# 15V7A.net
KiCad netlist of a schematic drawn in Altium Designer
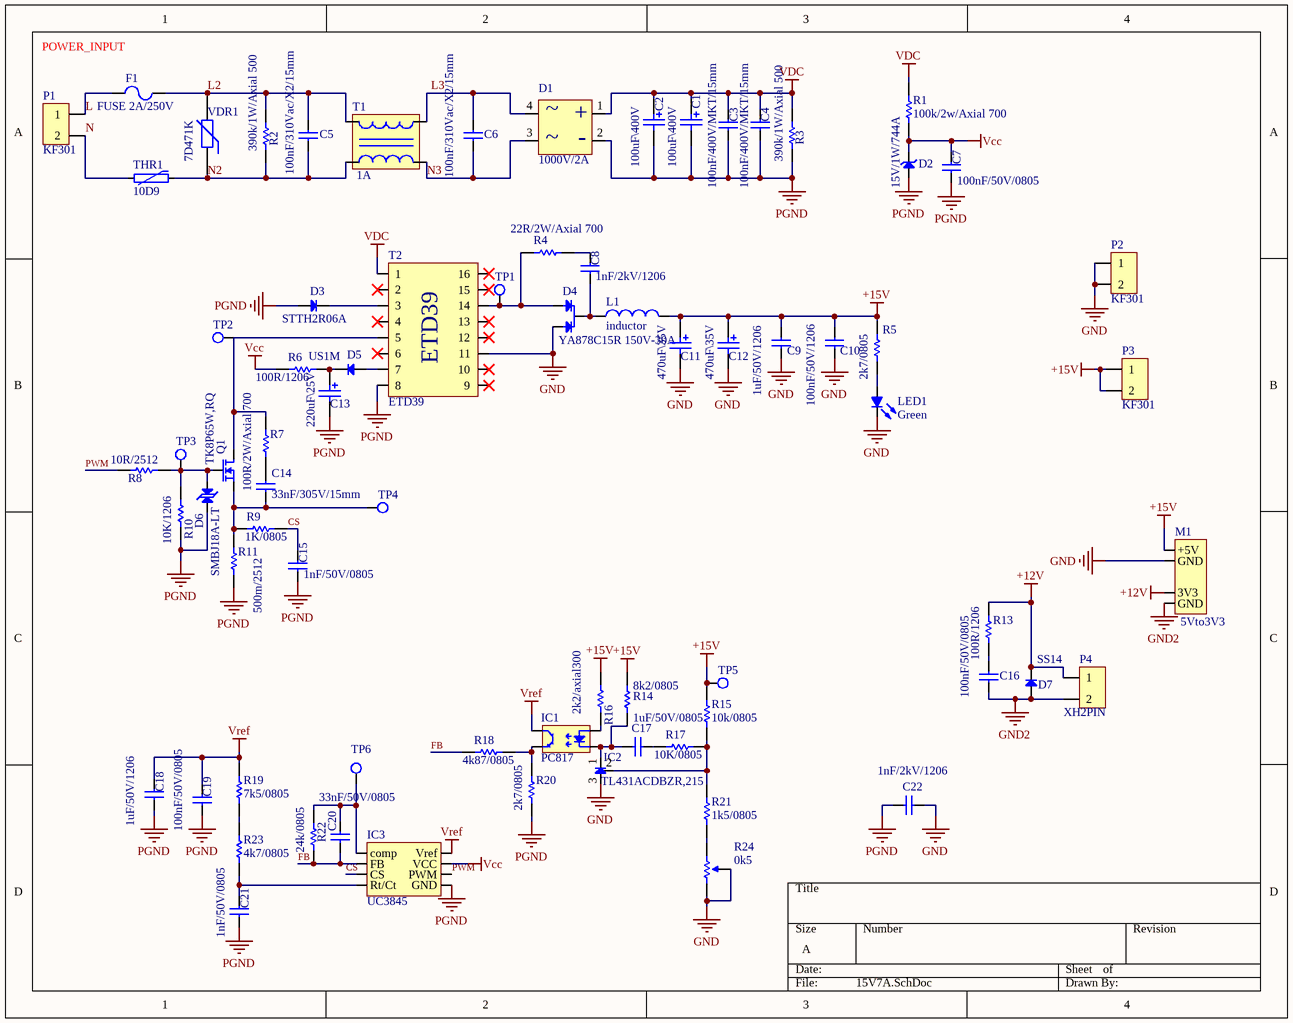
[diagram p0: 15V7A.SchDoc]

(export (version "E")
  (design (tool "Eeschema 10.0.6"))
  (components
    (comp (ref "C1")
      (value "100u~{F}400V")
      (footprint "18.5x31 p = 7.5")
      (description "Polarized Capacitor (Radial)")
      (fields (field (name "PUBLISHER") "Altium Limited"))
      (libsource (lib "Schlib") (part "Cap Pol1"))
    )
    (comp (ref "C2")
      (value "100u~{F}400V")
      (footprint "18.5x31 p = 7.5")
      (description "Polarized Capacitor (Radial)")
      (fields (field (name "PUBLISHER") "Altium Limited"))
      (libsource (lib "Schlib") (part "Cap Pol1"))
    )
    (comp (ref "C3")
      (value "100nF/400V/MKT/15mm")
      (footprint "18.4x7.5 p =15")
      (description "Capacitor")
      (libsource (lib "Schlib") (part "Capacitor"))
    )
    (comp (ref "C4")
      (value "100nF/400V/MKT/15mm")
      (footprint "18.4x7.5 p =15")
      (description "Capacitor")
      (libsource (lib "Schlib") (part "Capacitor"))
    )
    (comp (ref "C5")
      (value "100nF/310Vac/X2/15mm")
      (footprint "0.1uF/275VAC/X@/15mm")
      (description "Capacitor")
      (libsource (lib "Schlib") (part "Capacitor"))
    )
    (comp (ref "C6")
      (value "100nF/310Vac/X2/15mm")
      (footprint "0.1uF/275VAC/X@/15mm")
      (description "Capacitor")
      (libsource (lib "Schlib") (part "Capacitor"))
    )
    (comp (ref "C7")
      (value "100nF/50V/0805")
      (footprint "CAP 0805")
      (description "Capacitor")
      (libsource (lib "Schlib") (part "Capacitor"))
    )
    (comp (ref "C8")
      (value "1nF/2kV/1206")
      (footprint "CAP 1206")
      (description "Capacitor")
      (libsource (lib "Schlib") (part "Capacitor"))
    )
    (comp (ref "C9")
      (value "1uF/50V/1206")
      (footprint "CAP 1206")
      (description "Capacitor")
      (libsource (lib "Schlib") (part "Capacitor"))
    )
    (comp (ref "C10")
      (value "100nF/50V/1206")
      (footprint "CAP 1206")
      (description "Capacitor")
      (libsource (lib "Schlib") (part "Capacitor"))
    )
    (comp (ref "C11")
      (value "470u~{F}35V")
      (footprint "10x12 p = 5")
      (description "Polarized Capacitor (Radial)")
      (fields (field (name "PUBLISHER") "Altium Limited"))
      (libsource (lib "Schlib") (part "Cap Pol1"))
    )
    (comp (ref "C12")
      (value "470u~{F}35V")
      (footprint "10x12 p = 5")
      (description "Polarized Capacitor (Radial)")
      (fields (field (name "PUBLISHER") "Altium Limited"))
      (libsource (lib "Schlib") (part "Cap Pol1"))
    )
    (comp (ref "C13")
      (value "220u~{F}25V")
      (footprint "cap 5*11,p=2")
      (description "Polarized Capacitor (Radial)")
      (fields (field (name "PUBLISHER") "Altium Limited"))
      (libsource (lib "Schlib") (part "Cap Pol1"))
    )
    (comp (ref "C14")
      (value "33nF/305V/15mm")
      (footprint "0.1uF/275VAC/X@/15mm")
      (description "Capacitor")
      (libsource (lib "Schlib") (part "Capacitor"))
    )
    (comp (ref "C15")
      (value "1nF/50V/0805")
      (footprint "CAP 0805")
      (description "Capacitor")
      (libsource (lib "Schlib") (part "Capacitor"))
    )
    (comp (ref "C16")
      (value "100nF/50V/0805")
      (footprint "CAP 0805")
      (description "Capacitor")
      (libsource (lib "Schlib") (part "Capacitor"))
    )
    (comp (ref "C17")
      (value "1uF/50V/0805")
      (footprint "CAP 0805")
      (description "Capacitor")
      (libsource (lib "Schlib") (part "Capacitor"))
    )
    (comp (ref "C18")
      (value "1uF/50V/1206")
      (footprint "CAP 1206")
      (description "Capacitor")
      (libsource (lib "Schlib") (part "Capacitor"))
    )
    (comp (ref "C19")
      (value "100nF/50V/0805")
      (footprint "CAP 0805")
      (description "Capacitor")
      (libsource (lib "Schlib") (part "Capacitor"))
    )
    (comp (ref "C20")
      (value "33nF/50V/0805")
      (footprint "CAP 0805")
      (description "Capacitor")
      (libsource (lib "Schlib") (part "Capacitor"))
    )
    (comp (ref "C21")
      (value "1nF/50V/0805")
      (footprint "CAP 0805")
      (description "Capacitor")
      (libsource (lib "Schlib") (part "Capacitor"))
    )
    (comp (ref "C22")
      (value "1nF/2kV/1206")
      (footprint "CAP 1206")
      (description "Capacitor")
      (libsource (lib "Schlib") (part "Capacitor"))
    )
    (comp (ref "D1") (value "1000V/2A") (footprint "ABS210") (libsource (lib "Schlib") (part "br-diode")))
    (comp (ref "D2") (value "15V/1W/744A") (footprint "SMA") (libsource (lib "Schlib") (part "ZENER")))
    (comp (ref "D3") (value "STTH2R06A") (footprint "SMA") (libsource (lib "Schlib") (part "Diode")))
    (comp (ref "D4")
      (value "YA878C15R 150V-30A")
      (footprint "TO-220")
      (libsource (lib "Schlib") (part "Diode 2*1 CA"))
    )
    (comp (ref "D5") (value "US1M") (footprint "SMA") (libsource (lib "Schlib") (part "Diode")))
    (comp (ref "D6")
      (value "SMBJ18A-LT")
      (footprint "SMB(DO-214AA)")
      (description "18v-20A")
      (libsource (lib "Schlib") (part "TVS-BIPOLAR"))
    )
    (comp (ref "D7") (value "SS14") (footprint "SMA") (libsource (lib "Schlib") (part "Diode")))
    (comp (ref "F1")
      (value "FUSE 2A/250V")
      (footprint "smd Fuse Block 155 OMNI-BLOK")
      (description "Fuse")
      (libsource (lib "Fx7sam") (part "Fuse"))
    )
    (comp (ref "IC1") (value "PC817") (footprint "pc817") (libsource (lib "Schlib") (part "PC817")))
    (comp (ref "IC2")
      (value "TL431ACDBZR,215")
      (footprint "SOT-23")
      (libsource (lib "Schlib") (part "TL431DBZ"))
    )
    (comp (ref "IC3") (value "UC3845") (footprint "SO8") (libsource (lib "Schlib") (part "UC3845")))
    (comp (ref "L1")
      (value "inductor")
      (footprint "50uh/kt130-26")
      (libsource (lib "Schlib") (part "inductor"))
    )
    (comp (ref "LED1")
      (value "LED 3mm/Green")
      (footprint "LED 3mm")
      (description "Typical LED")
      (fields (field (name "COLOR") "Green"))
      (libsource (lib "TL494 12V-20A-KARA") (part "LED"))
    )
    (comp (ref "M1") (value "5Vto3V3") (footprint "5Vto3V3") (libsource (lib "Schlib") (part "5Vto3V3")))
    (comp (ref "P1")
      (value "KF301")
      (footprint "KF301-5.0-2P")
      (description "RELAY")
      (fields (field (name "PUBLISHER") "Altium Limited"))
      (libsource (lib "Schlib") (part "Header 2H"))
    )
    (comp (ref "P2")
      (value "KF301")
      (footprint "KF301-5.0-2P")
      (description "RELAY")
      (fields (field (name "PUBLISHER") "Altium Limited"))
      (libsource (lib "") (part "Header 2H_1"))
    )
    (comp (ref "P3")
      (value "KF301")
      (footprint "KF301-5.0-2P")
      (description "RELAY")
      (fields (field (name "PUBLISHER") "Altium Limited"))
      (libsource (lib "") (part "Header 2H_1"))
    )
    (comp (ref "P4")
      (value "XH2PIN")
      (footprint "XH-2Pin")
      (description "RELAY")
      (fields (field (name "PUBLISHER") "Altium Limited"))
      (libsource (lib "") (part "Header 2H_1"))
    )
    (comp (ref "Q1")
      (value "TK8P65W,RQ")
      (footprint "DPAK-3")
      (libsource (lib "Schlib") (part "Mosfet N-channel"))
    )
    (comp (ref "R1")
      (value "100k/2w/Axial 700")
      (footprint "Axial 0.7")
      (libsource (lib "Schlib") (part "Res"))
    )
    (comp (ref "R2")
      (value "390k/1W/Axial 500")
      (footprint "RES 2512")
      (libsource (lib "Schlib") (part "Res"))
    )
    (comp (ref "R3")
      (value "390k/1W/Axial 500")
      (footprint "RES 2512")
      (libsource (lib "Schlib") (part "Res"))
    )
    (comp (ref "R4")
      (value "22R/2W/Axial 700")
      (footprint "Axial 0.7")
      (description "Resistor")
      (fields (field (name "PUBLISHER") "Altium Limited"))
      (libsource (lib "Miscellaneous Devices") (part "Res1"))
    )
    (comp (ref "R5")
      (value "2k7/0805")
      (footprint "RES 0805")
      (description "Resistor")
      (fields (field (name "PUBLISHER") "Altium Limited"))
      (libsource (lib "Miscellaneous Devices") (part "Res1"))
    )
    (comp (ref "R6")
      (value "100R/1206")
      (footprint "RES 1206")
      (description "Resistor")
      (fields (field (name "PUBLISHER") "Altium Limited"))
      (libsource (lib "Miscellaneous Devices") (part "Res1"))
    )
    (comp (ref "R7")
      (value "100R/2W/Axial 700")
      (footprint "Axial 0.7")
      (description "Resistor")
      (fields (field (name "PUBLISHER") "Altium Limited"))
      (libsource (lib "Miscellaneous Devices") (part "Res1"))
    )
    (comp (ref "R8")
      (value "10R/2512")
      (footprint "RES 2512")
      (description "Resistor")
      (fields (field (name "PUBLISHER") "Altium Limited"))
      (libsource (lib "Miscellaneous Devices") (part "Res1"))
    )
    (comp (ref "R9")
      (value "1K/0805")
      (footprint "RES 0805")
      (description "Resistor")
      (fields (field (name "PUBLISHER") "Altium Limited"))
      (libsource (lib "Miscellaneous Devices") (part "Res1"))
    )
    (comp (ref "R10")
      (value "10K/1206")
      (footprint "RES 1206")
      (description "Resistor")
      (fields (field (name "PUBLISHER") "Altium Limited"))
      (libsource (lib "Miscellaneous Devices") (part "Res1"))
    )
    (comp (ref "R11")
      (value "500m/2512")
      (footprint "RES 1206")
      (description "Resistor")
      (fields (field (name "PUBLISHER") "Altium Limited"))
      (libsource (lib "Miscellaneous Devices") (part "Res1"))
    )
    (comp (ref "R13") (value "100R/1206") (footprint "RES 1206") (libsource (lib "22") (part "Res 0.5 W")))
    (comp (ref "R14")
      (value "8k2/0805")
      (footprint "RES 0805")
      (description "Resistor")
      (fields (field (name "PUBLISHER") "Altium Limited"))
      (libsource (lib "Miscellaneous Devices") (part "Res1"))
    )
    (comp (ref "R15")
      (value "10k/0805")
      (footprint "RES 0805")
      (description "Resistor")
      (fields (field (name "PUBLISHER") "Altium Limited"))
      (libsource (lib "Miscellaneous Devices") (part "Res1"))
    )
    (comp (ref "R16")
      (value "2k2/axial300")
      (footprint "Axial 0.3")
      (description "Resistor")
      (fields (field (name "PUBLISHER") "Altium Limited"))
      (libsource (lib "Miscellaneous Devices") (part "Res1"))
    )
    (comp (ref "R17")
      (value "10K/0805")
      (footprint "RES 0805")
      (description "Resistor")
      (fields (field (name "PUBLISHER") "Altium Limited"))
      (libsource (lib "Miscellaneous Devices") (part "Res1"))
    )
    (comp (ref "R18")
      (value "4k87/0805")
      (footprint "RES 0805")
      (description "Resistor")
      (fields (field (name "PUBLISHER") "Altium Limited"))
      (libsource (lib "Miscellaneous Devices") (part "Res1"))
    )
    (comp (ref "R19")
      (value "7k5/0805")
      (footprint "RES 0805")
      (description "Resistor")
      (fields (field (name "PUBLISHER") "Altium Limited"))
      (libsource (lib "Miscellaneous Devices") (part "Res1"))
    )
    (comp (ref "R20")
      (value "2k7/0805")
      (footprint "RES 0805")
      (description "Resistor")
      (fields (field (name "PUBLISHER") "Altium Limited"))
      (libsource (lib "Miscellaneous Devices") (part "Res1"))
    )
    (comp (ref "R21")
      (value "1k5/0805")
      (footprint "RES 0805")
      (description "Resistor")
      (fields (field (name "PUBLISHER") "Altium Limited"))
      (libsource (lib "Miscellaneous Devices") (part "Res1"))
    )
    (comp (ref "R22")
      (value "24k/0805")
      (footprint "RES 0805")
      (description "Resistor")
      (fields (field (name "PUBLISHER") "Altium Limited"))
      (libsource (lib "Miscellaneous Devices") (part "Res1"))
    )
    (comp (ref "R23")
      (value "4k7/0805")
      (footprint "RES 0805")
      (description "Resistor")
      (fields (field (name "PUBLISHER") "Altium Limited"))
      (libsource (lib "Miscellaneous Devices") (part "Res1"))
    )
    (comp (ref "R24")
      (value "0k5")
      (footprint "trimmer resistor thd")
      (libsource (lib "Schlib") (part "POT"))
    )
    (comp (ref "T1")
      (value "1A")
      (footprint "UF 10")
      (description "Line Filter")
      (libsource (lib "Fx7sam") (part "Line Filter_01"))
    )
    (comp (ref "T2") (value "ETD39") (footprint "ETD39 - forward") (libsource (lib "Schlib") (part "ETD39")))
    (comp (ref "THR1")
      (value "10D9")
      (footprint "10D9")
      (description "NTC")
      (libsource (lib "CHARGER 99-02") (part "NTC"))
    )
    (comp (ref "TP1") (value "~") (footprint "TP") (libsource (lib "Schlib") (part "test-point")))
    (comp (ref "TP2") (value "~") (footprint "TP") (libsource (lib "Schlib") (part "test-point")))
    (comp (ref "TP3") (value "~") (footprint "TP") (libsource (lib "Schlib") (part "test-point")))
    (comp (ref "TP4") (value "~") (footprint "TP") (libsource (lib "Schlib") (part "test-point")))
    (comp (ref "TP5") (value "~") (footprint "TP") (libsource (lib "Schlib") (part "test-point")))
    (comp (ref "TP6") (value "~") (footprint "TP") (libsource (lib "Schlib") (part "test-point")))
    (comp (ref "VDR1")
      (value "7D471K")
      (footprint "7D471K")
      (description "VARISTORS")
      (fields
        (field (name "MANUFACTURER") "china-canada-philipina")
        (field (name "DESIGNER") "Abbas Basereh")
        (field (name "PUBLISHER") "ABBAS BASEREH")
      )
      (libsource (lib "reza babatabar (8)") (part "VARISTOR (VDR)"))
    )
  )
  (nets
    (net (code "1") (name "+12V") (class "Default")
      (node (ref "D7") (pin "2") (pinfunction "2_2") (pintype "passive"))
      (node (ref "M1") (pin "3") (pinfunction "3V3_3") (pintype "passive"))
      (node (ref "P4") (pin "1") (pinfunction "1_1") (pintype "passive"))
      (node (ref "R13") (pin "1") (pinfunction "1_1") (pintype "passive"))
    )
    (net (code "2") (name "+15V") (class "Default")
      (node (ref "C10") (pin "2") (pinfunction "-_2") (pintype "passive"))
      (node (ref "C11") (pin "1") (pinfunction "1_1") (pintype "passive"))
      (node (ref "C12") (pin "1") (pinfunction "1_1") (pintype "passive"))
      (node (ref "C9") (pin "2") (pinfunction "-_2") (pintype "passive"))
      (node (ref "L1") (pin "2") (pinfunction "2_2") (pintype "passive"))
      (node (ref "M1") (pin "1") (pinfunction "+5V_1") (pintype "passive"))
      (node (ref "P3") (pin "1") (pinfunction "1_1") (pintype "passive"))
      (node (ref "P3") (pin "2") (pinfunction "2_2") (pintype "passive"))
      (node (ref "R14") (pin "1") (pinfunction "1_1") (pintype "passive"))
      (node (ref "R15") (pin "1") (pinfunction "1_1") (pintype "passive"))
      (node (ref "R16") (pin "1") (pinfunction "1_1") (pintype "passive"))
      (node (ref "R5") (pin "1") (pinfunction "1_1") (pintype "passive"))
      (node (ref "TP5") (pin "1") (pintype "passive"))
    )
    (net (code "3") (name "/CS") (class "Default")
      (node (ref "C15") (pin "2") (pinfunction "-_2") (pintype "passive"))
      (node (ref "IC3") (pin "3") (pinfunction "CS_3") (pintype "passive"))
      (node (ref "R9") (pin "1") (pinfunction "1_1") (pintype "passive"))
    )
    (net (code "4") (name "/FB") (class "Default")
      (node (ref "C20") (pin "1") (pinfunction "+_1") (pintype "passive"))
      (node (ref "IC3") (pin "2") (pinfunction "FB_2") (pintype "passive"))
      (node (ref "R18") (pin "1") (pinfunction "1_1") (pintype "passive"))
      (node (ref "R22") (pin "2") (pinfunction "2_2") (pintype "passive"))
    )
    (net (code "5") (name "/L") (class "Default")
      (node (ref "F1") (pin "2") (pinfunction "2_2") (pintype "passive"))
      (node (ref "P1") (pin "1") (pinfunction "1_1") (pintype "passive"))
    )
    (net (code "6") (name "/L2") (class "Default")
      (node (ref "C5") (pin "1") (pinfunction "+_1") (pintype "passive"))
      (node (ref "F1") (pin "1") (pinfunction "1_1") (pintype "passive"))
      (node (ref "R2") (pin "2") (pinfunction "2_2") (pintype "passive"))
      (node (ref "T1") (pin "1") (pinfunction "1_1") (pintype "passive"))
      (node (ref "VDR1") (pin "2") (pinfunction "2_2") (pintype "passive"))
    )
    (net (code "7") (name "/L3") (class "Default")
      (node (ref "C6") (pin "2") (pinfunction "-_2") (pintype "passive"))
      (node (ref "D1") (pin "4") (pinfunction "4_4") (pintype "passive"))
      (node (ref "T1") (pin "4") (pinfunction "4_4") (pintype "passive"))
    )
    (net (code "8") (name "/N") (class "Default")
      (node (ref "P1") (pin "2") (pinfunction "2_2") (pintype "passive"))
      (node (ref "THR1") (pin "2") (pinfunction "2_2") (pintype "passive"))
    )
    (net (code "9") (name "/N2") (class "Default")
      (node (ref "C5") (pin "2") (pinfunction "-_2") (pintype "passive"))
      (node (ref "R2") (pin "1") (pinfunction "1_1") (pintype "passive"))
      (node (ref "T1") (pin "2") (pinfunction "2_2") (pintype "passive"))
      (node (ref "THR1") (pin "1") (pinfunction "1_1") (pintype "passive"))
      (node (ref "VDR1") (pin "1") (pinfunction "1_1") (pintype "passive"))
    )
    (net (code "10") (name "/N3") (class "Default")
      (node (ref "C6") (pin "1") (pinfunction "+_1") (pintype "passive"))
      (node (ref "D1") (pin "3") (pinfunction "3_3") (pintype "passive"))
      (node (ref "T1") (pin "3") (pinfunction "3_3") (pintype "passive"))
    )
    (net (code "11") (name "/PWM") (class "Default")
      (node (ref "IC3") (pin "6") (pinfunction "PWM_6") (pintype "passive"))
      (node (ref "R8") (pin "1") (pinfunction "1_1") (pintype "passive"))
    )
    (net (code "12") (name "GND") (class "Default")
      (node (ref "C10") (pin "1") (pinfunction "+_1") (pintype "passive"))
      (node (ref "C11") (pin "2") (pinfunction "2_2") (pintype "passive"))
      (node (ref "C12") (pin "2") (pinfunction "2_2") (pintype "passive"))
      (node (ref "C22") (pin "1") (pinfunction "+_1") (pintype "passive"))
      (node (ref "C9") (pin "1") (pinfunction "+_1") (pintype "passive"))
      (node (ref "D4") (pin "1") (pinfunction "1_1") (pintype "passive"))
      (node (ref "IC2") (pin "3") (pinfunction "Anode_3") (pintype "passive"))
      (node (ref "LED1") (pin "2") (pinfunction "K_2") (pintype "passive"))
      (node (ref "M1") (pin "2") (pinfunction "GND_2") (pintype "passive"))
      (node (ref "P2") (pin "1") (pinfunction "1_1") (pintype "passive"))
      (node (ref "P2") (pin "2") (pinfunction "2_2") (pintype "passive"))
      (node (ref "R24") (pin "2") (pinfunction "2_2") (pintype "passive"))
      (node (ref "R24") (pin "3") (pinfunction "3_3") (pintype "passive"))
      (node (ref "T2") (pin "11") (pinfunction "11_11") (pintype "passive"))
    )
    (net (code "13") (name "GND2") (class "Default")
      (node (ref "C16") (pin "1") (pinfunction "+_1") (pintype "passive"))
      (node (ref "D7") (pin "1") (pinfunction "1_1") (pintype "passive"))
      (node (ref "M1") (pin "4") (pinfunction "GND_4") (pintype "passive"))
      (node (ref "P4") (pin "2") (pinfunction "2_2") (pintype "passive"))
    )
    (net (code "14") (name "Net-(C8-+)") (class "Default")
      (node (ref "C8") (pin "1") (pinfunction "+_1") (pintype "passive"))
      (node (ref "D4") (pin "2") (pinfunction "2_2") (pintype "passive"))
      (node (ref "L1") (pin "1") (pinfunction "1_1") (pintype "passive"))
    )
    (net (code "15") (name "Net-(C8--)") (class "Default")
      (node (ref "C8") (pin "2") (pinfunction "-_2") (pintype "passive"))
      (node (ref "R4") (pin "1") (pinfunction "1_1") (pintype "passive"))
    )
    (net (code "16") (name "Net-(C13-Pad1)") (class "Default")
      (node (ref "C13") (pin "1") (pinfunction "1_1") (pintype "passive"))
      (node (ref "D5") (pin "2") (pinfunction "2_2") (pintype "passive"))
      (node (ref "R6") (pin "2") (pinfunction "2_2") (pintype "passive"))
    )
    (net (code "17") (name "Net-(C14-+)") (class "Default")
      (node (ref "C14") (pin "1") (pinfunction "+_1") (pintype "passive"))
      (node (ref "Q1") (pin "3") (pinfunction "S_3") (pintype "passive"))
      (node (ref "R11") (pin "1") (pinfunction "1_1") (pintype "passive"))
      (node (ref "R9") (pin "2") (pinfunction "2_2") (pintype "passive"))
      (node (ref "TP4") (pin "1") (pintype "passive"))
    )
    (net (code "18") (name "Net-(C14--)") (class "Default")
      (node (ref "C14") (pin "2") (pinfunction "-_2") (pintype "passive"))
      (node (ref "R7") (pin "2") (pinfunction "2_2") (pintype "passive"))
    )
    (net (code "19") (name "Net-(C16--)") (class "Default")
      (node (ref "C16") (pin "2") (pinfunction "-_2") (pintype "passive"))
      (node (ref "R13") (pin "2") (pinfunction "2_2") (pintype "passive"))
    )
    (net (code "20") (name "Net-(C17-+)") (class "Default")
      (node (ref "C17") (pin "1") (pinfunction "+_1") (pintype "passive"))
      (node (ref "R17") (pin "1") (pinfunction "1_1") (pintype "passive"))
    )
    (net (code "21") (name "Net-(C17--)") (class "Default")
      (node (ref "C17") (pin "2") (pinfunction "-_2") (pintype "passive"))
      (node (ref "IC1") (pin "2") (pinfunction "Cathode_2") (pintype "passive"))
      (node (ref "IC2") (pin "1") (pinfunction "cathode_1") (pintype "passive"))
      (node (ref "R14") (pin "2") (pinfunction "2_2") (pintype "passive"))
    )
    (net (code "22") (name "Net-(C20--)") (class "Default")
      (node (ref "C20") (pin "2") (pinfunction "-_2") (pintype "passive"))
      (node (ref "IC3") (pin "1") (pinfunction "comp_1") (pintype "passive"))
      (node (ref "R22") (pin "1") (pinfunction "1_1") (pintype "passive"))
      (node (ref "TP6") (pin "1") (pintype "passive"))
    )
    (net (code "23") (name "Net-(C21--)") (class "Default")
      (node (ref "C21") (pin "2") (pinfunction "-_2") (pintype "passive"))
      (node (ref "IC3") (pin "4") (pinfunction "Rt/Ct_4") (pintype "passive"))
      (node (ref "R23") (pin "2") (pinfunction "2_2") (pintype "passive"))
    )
    (net (code "24") (name "Net-(D3-Pad2)") (class "Default")
      (node (ref "D3") (pin "2") (pinfunction "2_2") (pintype "passive"))
      (node (ref "T2") (pin "3") (pinfunction "3_3") (pintype "passive"))
    )
    (net (code "25") (name "Net-(D4-Pad3)") (class "Default")
      (node (ref "D4") (pin "3") (pinfunction "3_3") (pintype "passive"))
      (node (ref "R4") (pin "2") (pinfunction "2_2") (pintype "passive"))
      (node (ref "T2") (pin "14") (pinfunction "14_14") (pintype "passive"))
      (node (ref "TP1") (pin "1") (pintype "passive"))
    )
    (net (code "26") (name "Net-(D5-Pad1)") (class "Default")
      (node (ref "D5") (pin "1") (pinfunction "1_1") (pintype "passive"))
      (node (ref "T2") (pin "7") (pinfunction "7_7") (pintype "passive"))
    )
    (net (code "27") (name "Net-(IC1-Anode)") (class "Default")
      (node (ref "IC1") (pin "1") (pinfunction "Anode_1") (pintype "passive"))
      (node (ref "R16") (pin "2") (pinfunction "2_2") (pintype "passive"))
    )
    (net (code "28") (name "Net-(IC1-Emitter)") (class "Default")
      (node (ref "IC1") (pin "3") (pinfunction "Emitter_3") (pintype "passive"))
      (node (ref "R18") (pin "2") (pinfunction "2_2") (pintype "passive"))
      (node (ref "R20") (pin "1") (pinfunction "1_1") (pintype "passive"))
    )
    (net (code "29") (name "Net-(IC2-ref)") (class "Default")
      (node (ref "IC2") (pin "2") (pinfunction "ref_2") (pintype "passive"))
      (node (ref "R15") (pin "2") (pinfunction "2_2") (pintype "passive"))
      (node (ref "R17") (pin "2") (pinfunction "2_2") (pintype "passive"))
      (node (ref "R21") (pin "1") (pinfunction "1_1") (pintype "passive"))
    )
    (net (code "30") (name "Net-(LED1-A)") (class "Default")
      (node (ref "LED1") (pin "1") (pinfunction "A_1") (pintype "passive"))
      (node (ref "R5") (pin "2") (pinfunction "2_2") (pintype "passive"))
    )
    (net (code "31") (name "Net-(Q1-D)") (class "Default")
      (node (ref "Q1") (pin "2") (pinfunction "D_2") (pintype "passive"))
      (node (ref "R7") (pin "1") (pinfunction "1_1") (pintype "passive"))
      (node (ref "T2") (pin "5") (pinfunction "5_5") (pintype "passive"))
      (node (ref "TP2") (pin "1") (pintype "passive"))
    )
    (net (code "32") (name "Net-(Q1-G)") (class "Default")
      (node (ref "D6") (pin "1") (pinfunction "1_1") (pintype "passive"))
      (node (ref "Q1") (pin "1") (pinfunction "G_1") (pintype "passive"))
      (node (ref "R10") (pin "1") (pinfunction "1_1") (pintype "passive"))
      (node (ref "R8") (pin "2") (pinfunction "2_2") (pintype "passive"))
      (node (ref "TP3") (pin "1") (pintype "passive"))
    )
    (net (code "33") (name "Net-(R19-Pad2)") (class "Default")
      (node (ref "R19") (pin "2") (pinfunction "2_2") (pintype "passive"))
      (node (ref "R23") (pin "1") (pinfunction "1_1") (pintype "passive"))
    )
    (net (code "34") (name "Net-(R21-Pad2)") (class "Default")
      (node (ref "R21") (pin "2") (pinfunction "2_2") (pintype "passive"))
      (node (ref "R24") (pin "1") (pinfunction "1_1") (pintype "passive"))
    )
    (net (code "35") (name "PGND") (class "Default")
      (node (ref "C1") (pin "2") (pinfunction "2_2") (pintype "passive"))
      (node (ref "C13") (pin "2") (pinfunction "2_2") (pintype "passive"))
      (node (ref "C15") (pin "1") (pinfunction "+_1") (pintype "passive"))
      (node (ref "C18") (pin "1") (pinfunction "+_1") (pintype "passive"))
      (node (ref "C19") (pin "1") (pinfunction "+_1") (pintype "passive"))
      (node (ref "C2") (pin "2") (pinfunction "2_2") (pintype "passive"))
      (node (ref "C21") (pin "1") (pinfunction "+_1") (pintype "passive"))
      (node (ref "C22") (pin "2") (pinfunction "-_2") (pintype "passive"))
      (node (ref "C3") (pin "1") (pinfunction "+_1") (pintype "passive"))
      (node (ref "C4") (pin "1") (pinfunction "+_1") (pintype "passive"))
      (node (ref "C7") (pin "1") (pinfunction "+_1") (pintype "passive"))
      (node (ref "D1") (pin "2") (pinfunction "2_2") (pintype "passive"))
      (node (ref "D2") (pin "1") (pinfunction "A_1") (pintype "passive"))
      (node (ref "D3") (pin "1") (pinfunction "1_1") (pintype "passive"))
      (node (ref "D6") (pin "2") (pinfunction "2_2") (pintype "passive"))
      (node (ref "IC3") (pin "5") (pinfunction "GND_5") (pintype "passive"))
      (node (ref "R10") (pin "2") (pinfunction "2_2") (pintype "passive"))
      (node (ref "R11") (pin "2") (pinfunction "2_2") (pintype "passive"))
      (node (ref "R20") (pin "2") (pinfunction "2_2") (pintype "passive"))
      (node (ref "R3") (pin "1") (pinfunction "1_1") (pintype "passive"))
      (node (ref "T2") (pin "8") (pinfunction "8_8") (pintype "passive"))
    )
    (net (code "36") (name "VDC") (class "Default")
      (node (ref "C1") (pin "1") (pinfunction "1_1") (pintype "passive"))
      (node (ref "C2") (pin "1") (pinfunction "1_1") (pintype "passive"))
      (node (ref "C3") (pin "2") (pinfunction "-_2") (pintype "passive"))
      (node (ref "C4") (pin "2") (pinfunction "-_2") (pintype "passive"))
      (node (ref "D1") (pin "1") (pinfunction "1_1") (pintype "passive"))
      (node (ref "R1") (pin "1") (pinfunction "1_1") (pintype "passive"))
      (node (ref "R3") (pin "2") (pinfunction "2_2") (pintype "passive"))
      (node (ref "T2") (pin "1") (pinfunction "1_1") (pintype "passive"))
    )
    (net (code "37") (name "Vcc") (class "Default")
      (node (ref "C7") (pin "2") (pinfunction "-_2") (pintype "passive"))
      (node (ref "D2") (pin "2") (pinfunction "K_2") (pintype "passive"))
      (node (ref "IC3") (pin "7") (pinfunction "VCC_7") (pintype "passive"))
      (node (ref "R1") (pin "2") (pinfunction "2_2") (pintype "passive"))
      (node (ref "R6") (pin "1") (pinfunction "1_1") (pintype "passive"))
    )
    (net (code "38") (name "Vref") (class "Default")
      (node (ref "C18") (pin "2") (pinfunction "-_2") (pintype "passive"))
      (node (ref "C19") (pin "2") (pinfunction "-_2") (pintype "passive"))
      (node (ref "IC1") (pin "4") (pinfunction "Collector_4") (pintype "passive"))
      (node (ref "IC3") (pin "8") (pinfunction "Vref_8") (pintype "passive"))
      (node (ref "R19") (pin "1") (pinfunction "1_1") (pintype "passive"))
    )
    (net (code "39") (name "unconnected-(T2-Pad2)") (class "Default")
      (node (ref "T2") (pin "2") (pinfunction "2_2") (pintype "passive+no_connect"))
    )
    (net (code "40") (name "unconnected-(T2-Pad4)") (class "Default")
      (node (ref "T2") (pin "4") (pinfunction "4_4") (pintype "passive+no_connect"))
    )
    (net (code "41") (name "unconnected-(T2-Pad6)") (class "Default")
      (node (ref "T2") (pin "6") (pinfunction "6_6") (pintype "passive+no_connect"))
    )
    (net (code "42") (name "unconnected-(T2-Pad9)") (class "Default")
      (node (ref "T2") (pin "9") (pinfunction "9_9") (pintype "passive+no_connect"))
    )
    (net (code "43") (name "unconnected-(T2-Pad10)") (class "Default")
      (node (ref "T2") (pin "10") (pinfunction "10_10") (pintype "passive+no_connect"))
    )
    (net (code "44") (name "unconnected-(T2-Pad12)") (class "Default")
      (node (ref "T2") (pin "12") (pinfunction "12_12") (pintype "passive+no_connect"))
    )
    (net (code "45") (name "unconnected-(T2-Pad13)") (class "Default")
      (node (ref "T2") (pin "13") (pinfunction "13_13") (pintype "passive+no_connect"))
    )
    (net (code "46") (name "unconnected-(T2-Pad15)") (class "Default")
      (node (ref "T2") (pin "15") (pinfunction "15_15") (pintype "passive+no_connect"))
    )
    (net (code "47") (name "unconnected-(T2-Pad16)") (class "Default")
      (node (ref "T2") (pin "16") (pinfunction "16_16") (pintype "passive+no_connect"))
    )
  )
)
